# Laser_Sign.net
KiCad netlist of a schematic drawn in EasyEDA
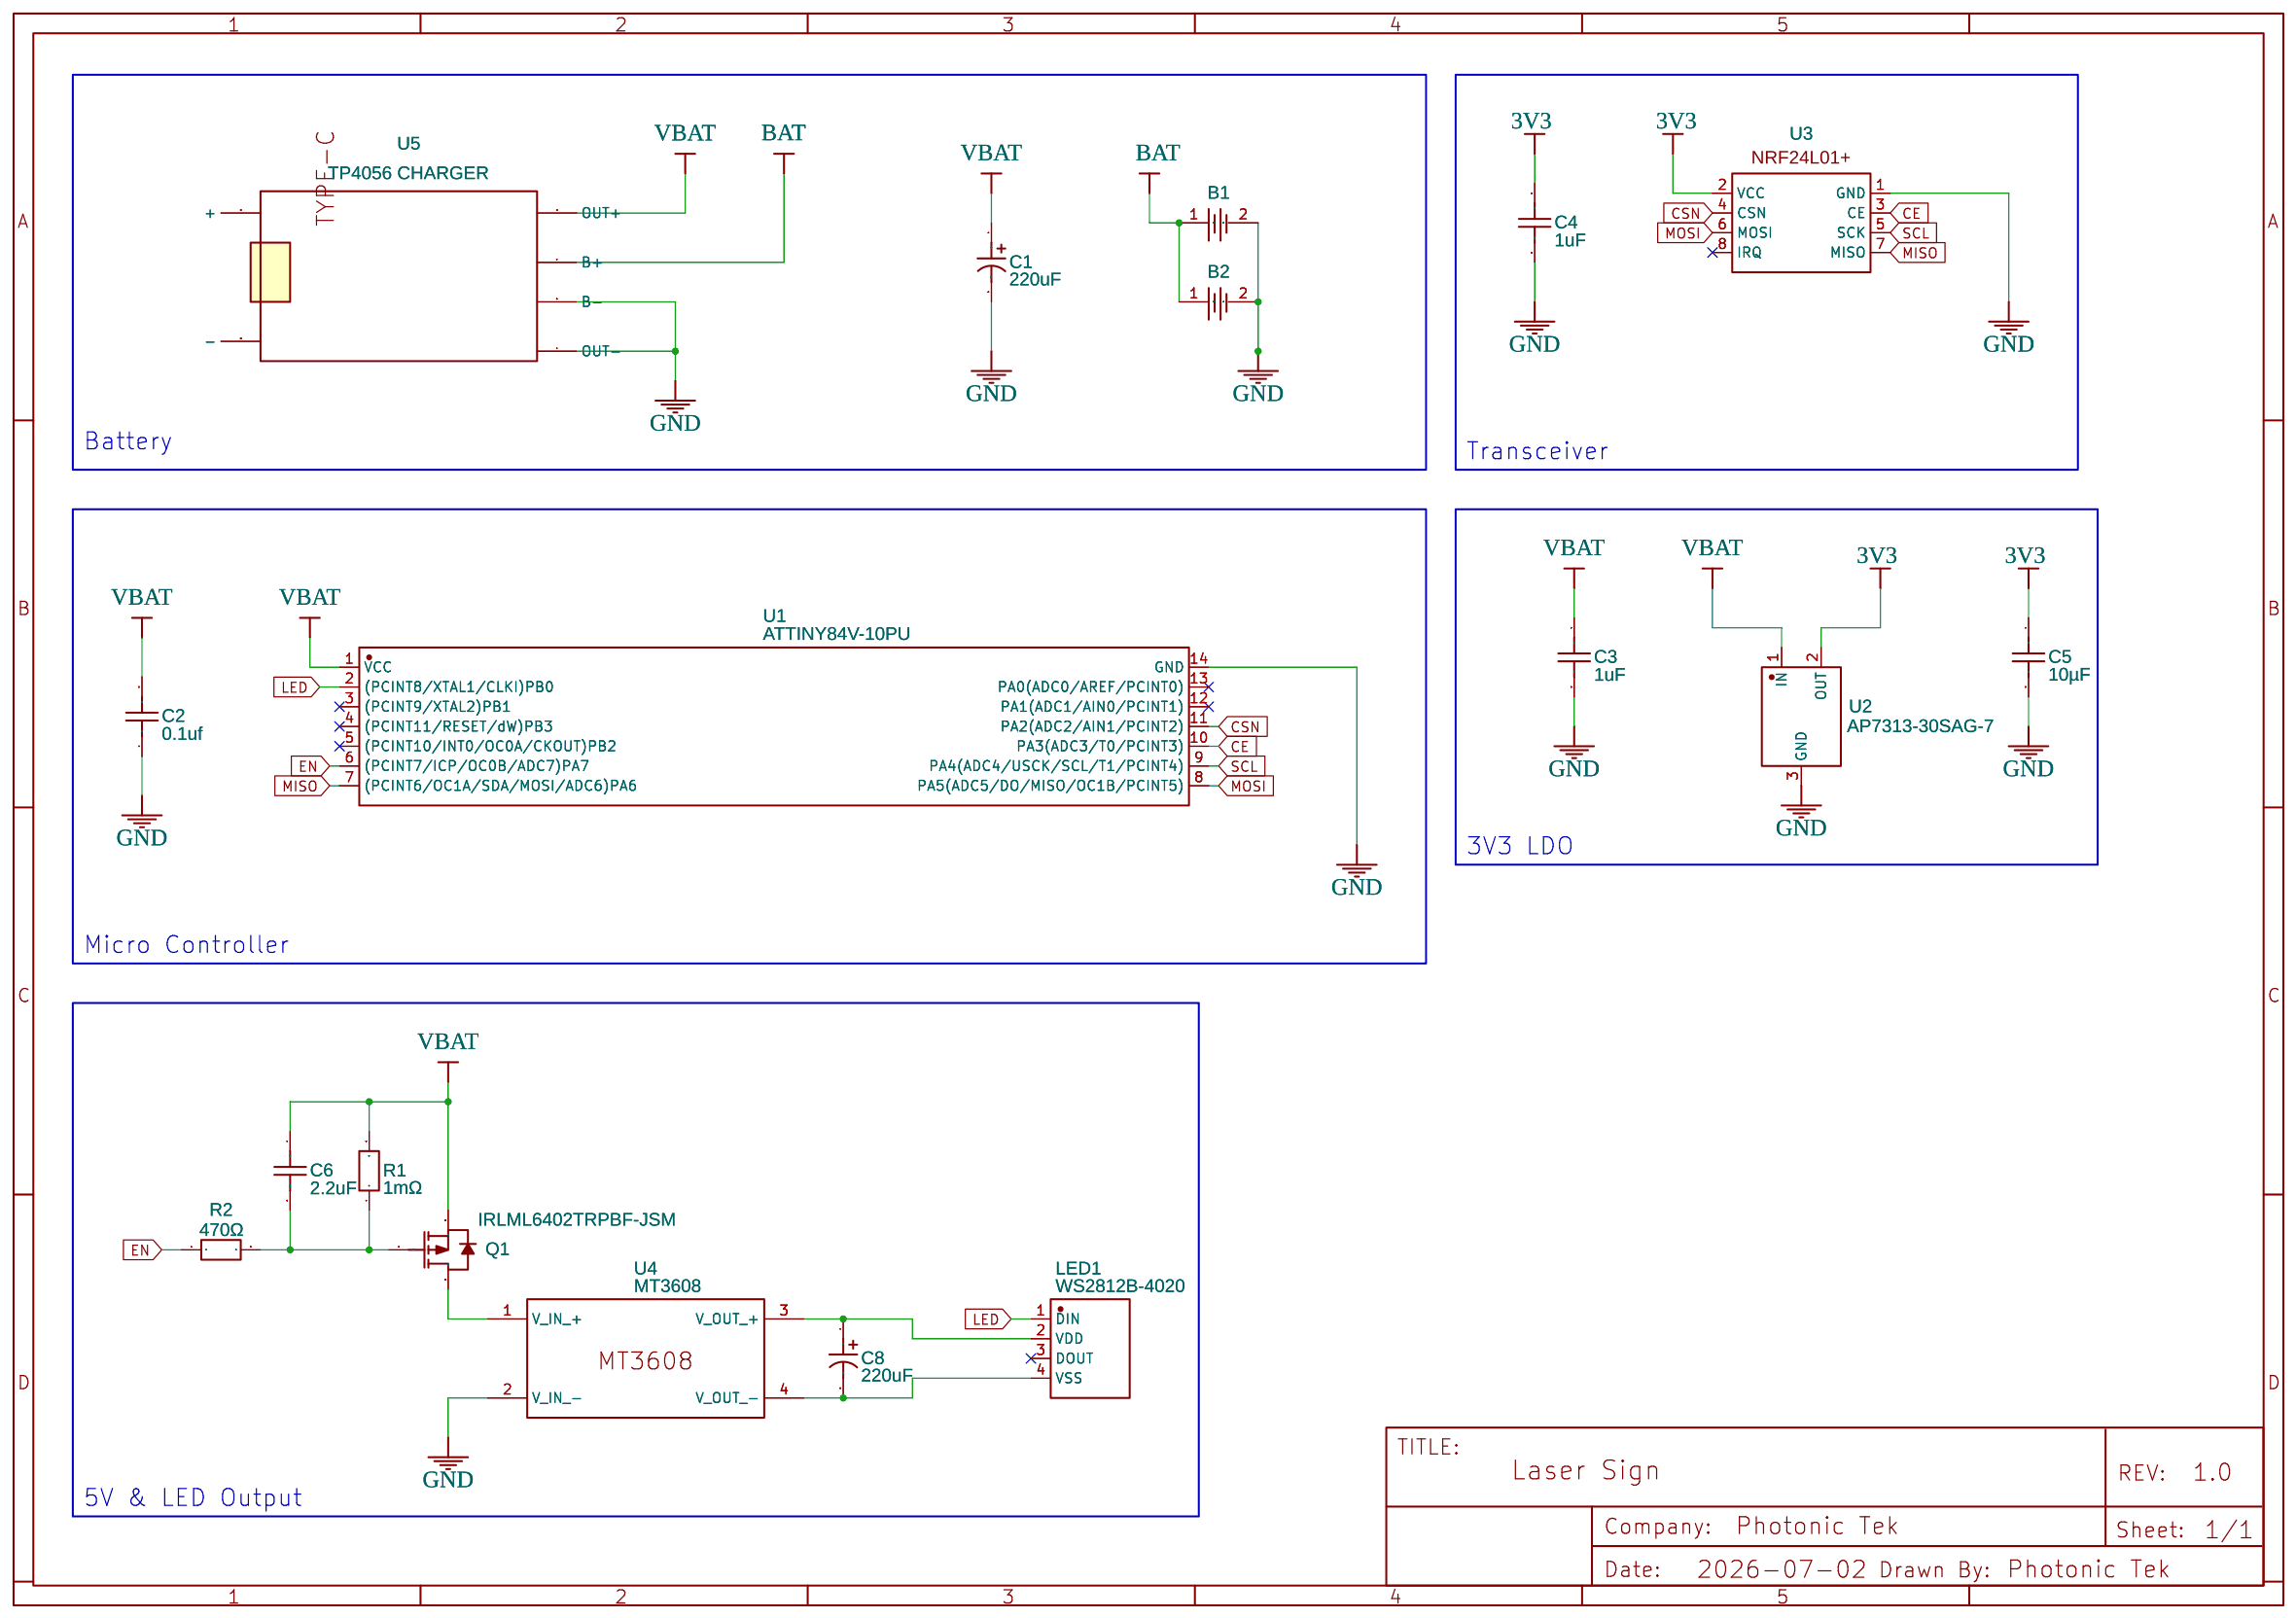
[diagram p0: Sheet_1]
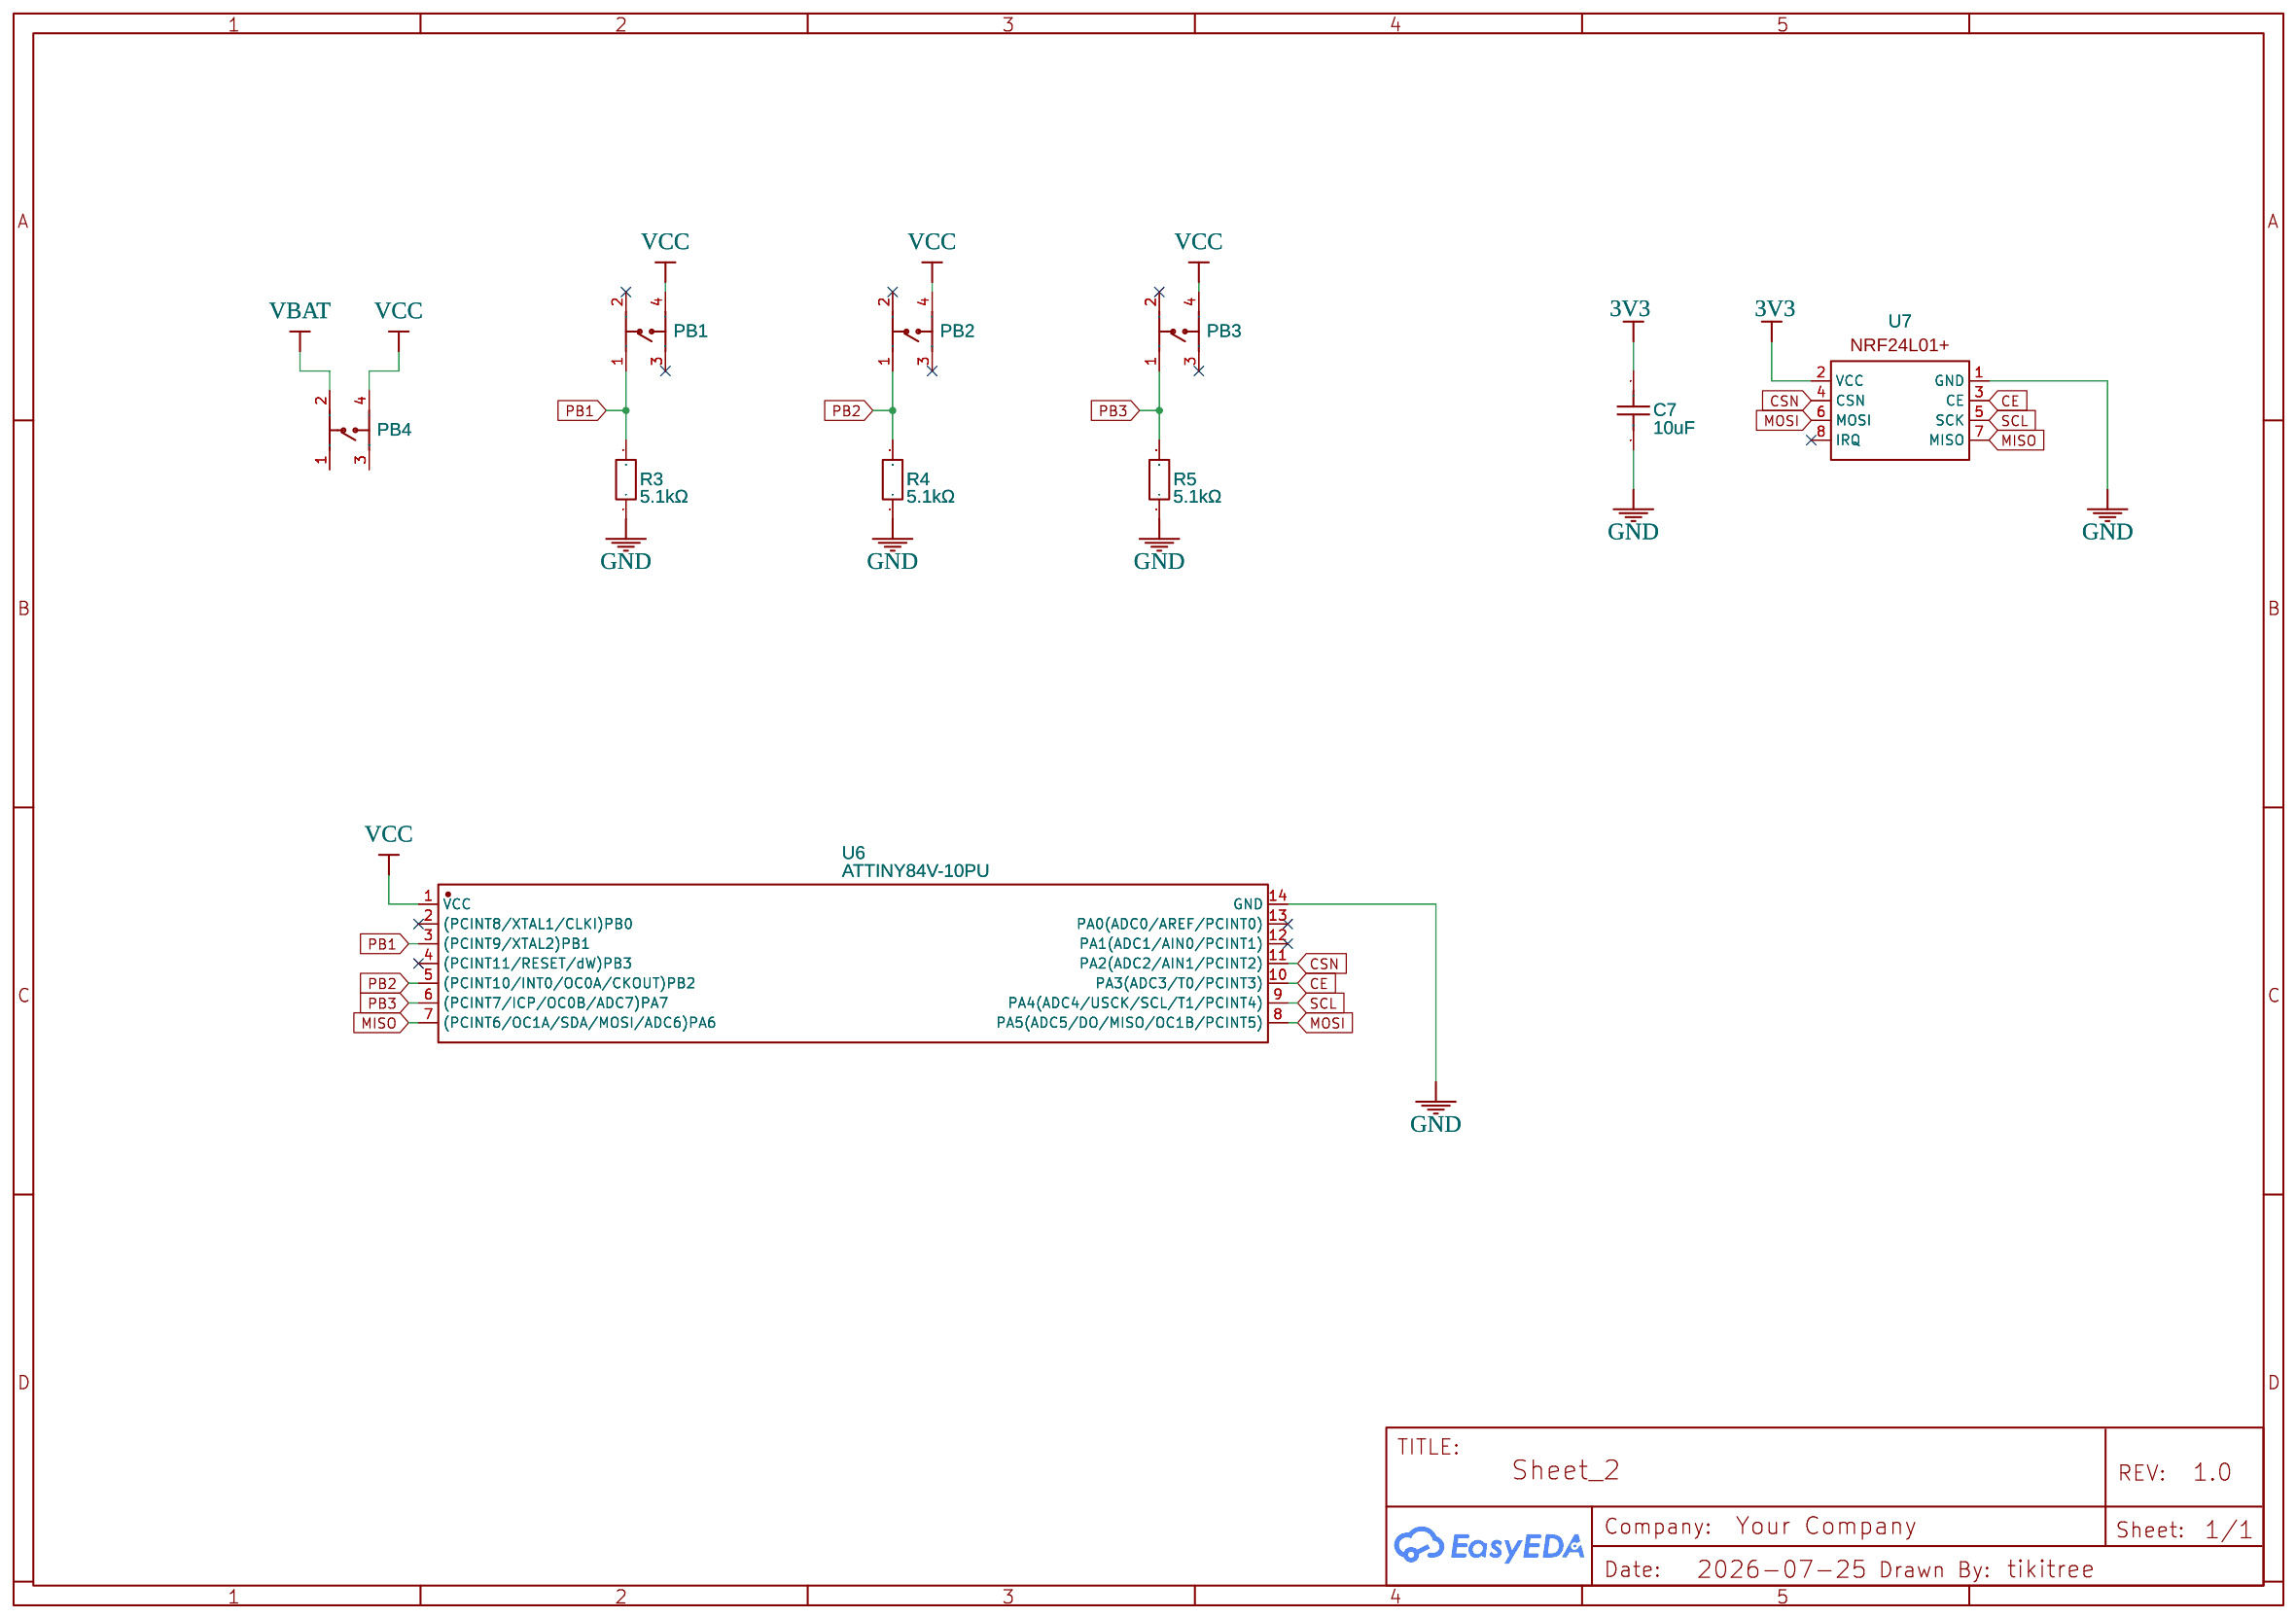
[diagram p1: Sheet_2]

(export (version "E")
  (design (tool "Eeschema 10.0.6"))
  (components
    (comp (ref "B1")
      (value "CR1220-2")
      (fields (field (name "Manufacturer") "Q&J"))
      (libsource (lib "") (part "CR1220-2"))
    )
    (comp (ref "B2")
      (value "CR1220-2")
      (fields (field (name "Manufacturer") "Q&J"))
      (libsource (lib "") (part "CR1220-2"))
    )
    (comp (ref "C1")
      (value "220uF")
      (fields (field (name "Manufacturer Part") "ERG50V220M10X13") (field (name "Manufacturer") "JIERR(捷而瑞)"))
      (libsource (lib "") (part "ERG50V220M10X13"))
    )
    (comp (ref "C2") (value "0.1uf") (libsource (lib "") (part "GE CERAMIC CAPACITOR")))
    (comp (ref "C3")
      (value "1uF")
      (fields (field (name "Manufacturer Part") "08053C105JAT2A") (field (name "Manufacturer") "KYOCERA AVX"))
      (libsource (lib "") (part "08053C105JAT2A"))
    )
    (comp (ref "C4")
      (value "1uF")
      (fields (field (name "Manufacturer Part") "08053C105JAT2A") (field (name "Manufacturer") "KYOCERA AVX"))
      (libsource (lib "") (part "08053C105JAT2A"))
    )
    (comp (ref "C5")
      (value "10µF")
      (fields
        (field (name "Manufacturer Part") "CL10A106MA8NRNC")
        (field (name "Manufacturer") "Samsung Electro-Mechanics")
      )
      (libsource (lib "") (part "CL10A106MA8NRNC"))
    )
    (comp (ref "C6")
      (value "2.2uF")
      (fields (field (name "Manufacturer Part") "08053C105JAT2A") (field (name "Manufacturer") "KYOCERA AVX"))
      (libsource (lib "") (part "08053C105JAT2A"))
    )
    (comp (ref "C8")
      (value "220uF")
      (fields (field (name "Manufacturer Part") "ERG50V220M10X13") (field (name "Manufacturer") "JIERR(捷而瑞)"))
      (libsource (lib "") (part "ERG50V220M10X13"))
    )
    (comp (ref "LED1")
      (value "WS2812B-4020")
      (fields (field (name "Manufacturer") "worldsemi"))
      (libsource (lib "") (part "WS2812B-4020"))
    )
    (comp (ref "Q1")
      (value "IRLML6402TRPBF-JSM")
      (fields (field (name "Manufacturer") "JSMSEMI(杰盛微)"))
      (libsource (lib "") (part "IRLML6402TRPBF-JSM"))
    )
    (comp (ref "R1")
      (value "1mΩ")
      (fields (field (name "Manufacturer Part") "TP810PW10K0JE") (field (name "Manufacturer") "Ohmite"))
      (libsource (lib "") (part "TP810PW10K0JE_1"))
    )
    (comp (ref "R2")
      (value "470Ω")
      (fields (field (name "Manufacturer Part") "TP810PW10K0JE") (field (name "Manufacturer") "Ohmite"))
      (libsource (lib "") (part "TP810PW10K0JE"))
    )
    (comp (ref "U1") (value "ATTINY84V-10PU") (libsource (lib "") (part "ATTINY84V-10PU")))
    (comp (ref "U2")
      (value "AP7313-30SAG-7")
      (fields (field (name "Manufacturer") "DIODES(美台)"))
      (libsource (lib "") (part "AP7313-30SAG-7"))
    )
    (comp (ref "U3") (value "NRF24L01+") (libsource (lib "") (part "NRF24L01+")))
    (comp (ref "U4") (value "MT3608") (libsource (lib "") (part "MT3608")))
    (comp (ref "U5")
      (value "TP4056 CHARGER")
      (fields (field (name "Manufacturer Part") "TP4056"))
      (libsource (lib "") (part "TP4056 CHARGING MODDULE"))
    )
    (comp (ref "C7")
      (value "10uF")
      (fields (field (name "Manufacturer Part") "08053C105JAT2A") (field (name "Manufacturer") "KYOCERA AVX"))
      (libsource (lib "") (part "08053C105JAT2A"))
    )
    (comp (ref "PB1")
      (value "TSC005A2526B")
      (fields (field (name "Manufacturer") "BZCN(博众电气)"))
      (libsource (lib "") (part "TSC005A2526B"))
    )
    (comp (ref "PB2")
      (value "TSC005A2526B")
      (fields (field (name "Manufacturer") "BZCN(博众电气)"))
      (libsource (lib "") (part "TSC005A2526B"))
    )
    (comp (ref "PB3")
      (value "TSC005A2526B")
      (fields (field (name "Manufacturer") "BZCN(博众电气)"))
      (libsource (lib "") (part "TSC005A2526B"))
    )
    (comp (ref "PB4")
      (value "TSC005A2526B")
      (fields (field (name "Manufacturer") "BZCN(博众电气)"))
      (libsource (lib "") (part "TSC005A2526B"))
    )
    (comp (ref "R3")
      (value "5.1kΩ")
      (fields (field (name "Manufacturer Part") "ERJP06J512V") (field (name "Manufacturer") "PANASONIC(松下)"))
      (libsource (lib "") (part "ERJP06J512V"))
    )
    (comp (ref "R4")
      (value "5.1kΩ")
      (fields (field (name "Manufacturer Part") "ERJP06J512V") (field (name "Manufacturer") "PANASONIC(松下)"))
      (libsource (lib "") (part "ERJP06J512V"))
    )
    (comp (ref "R5")
      (value "5.1kΩ")
      (fields (field (name "Manufacturer Part") "ERJP06J512V") (field (name "Manufacturer") "PANASONIC(松下)"))
      (libsource (lib "") (part "ERJP06J512V"))
    )
    (comp (ref "U6") (value "ATTINY84V-10PU") (libsource (lib "") (part "ATTINY84V-10PU")))
    (comp (ref "U7") (value "NRF24L01+") (libsource (lib "") (part "NRF24L01+")))
  )
  (nets
    (net (code "1") (name "3V3") (class "Default")
      (node (ref "C4") (pin "1") (pinfunction "1_1") (pintype "unspecified"))
      (node (ref "C5") (pin "1") (pinfunction "1_1") (pintype "unspecified"))
      (node (ref "C7") (pin "1") (pinfunction "1_1") (pintype "unspecified"))
      (node (ref "U2") (pin "2") (pinfunction "OUT_2") (pintype "unspecified"))
      (node (ref "U3") (pin "2") (pinfunction "VCC_2") (pintype "unspecified"))
      (node (ref "U7") (pin "2") (pinfunction "VCC_2") (pintype "unspecified"))
    )
    (net (code "2") (name "BAT") (class "Default")
      (node (ref "B1") (pin "1") (pinfunction "1_1") (pintype "input"))
      (node (ref "B2") (pin "1") (pinfunction "1_1") (pintype "input"))
    )
    (net (code "3") (name "CE") (class "Default")
      (node (ref "U1") (pin "10") (pinfunction "PA3(ADC3/T0/PCINT3)_10") (pintype "unspecified"))
      (node (ref "U3") (pin "3") (pinfunction "CE_3") (pintype "unspecified"))
      (node (ref "U6") (pin "10") (pinfunction "PA3(ADC3/T0/PCINT3)_10") (pintype "unspecified"))
      (node (ref "U7") (pin "3") (pinfunction "CE_3") (pintype "unspecified"))
    )
    (net (code "4") (name "CSN") (class "Default")
      (node (ref "U1") (pin "11") (pinfunction "PA2(ADC2/AIN1/PCINT2)_11") (pintype "unspecified"))
      (node (ref "U3") (pin "4") (pinfunction "CSN_4") (pintype "unspecified"))
      (node (ref "U6") (pin "11") (pinfunction "PA2(ADC2/AIN1/PCINT2)_11") (pintype "unspecified"))
      (node (ref "U7") (pin "4") (pinfunction "CSN_4") (pintype "unspecified"))
    )
    (net (code "5") (name "EN") (class "Default")
      (node (ref "R2") (pin "1") (pinfunction "1_1") (pintype "unspecified"))
      (node (ref "U1") (pin "6") (pinfunction "(PCINT7/ICP/OC0B/ADC7)PA7_6") (pintype "unspecified"))
    )
    (net (code "6") (name "GND") (class "Default")
      (node (ref "B1") (pin "2") (pinfunction "2_2") (pintype "input"))
      (node (ref "B2") (pin "2") (pinfunction "2_2") (pintype "input"))
      (node (ref "C1") (pin "2") (pinfunction "2_2") (pintype "input"))
      (node (ref "C2") (pin "1") (pinfunction "1_1") (pintype "unspecified"))
      (node (ref "C3") (pin "2") (pinfunction "2_2") (pintype "unspecified"))
      (node (ref "C4") (pin "2") (pinfunction "2_2") (pintype "unspecified"))
      (node (ref "C5") (pin "2") (pinfunction "2_2") (pintype "unspecified"))
      (node (ref "C7") (pin "2") (pinfunction "2_2") (pintype "unspecified"))
      (node (ref "R3") (pin "1") (pinfunction "1_1") (pintype "unspecified"))
      (node (ref "R4") (pin "1") (pinfunction "1_1") (pintype "unspecified"))
      (node (ref "R5") (pin "1") (pinfunction "1_1") (pintype "unspecified"))
      (node (ref "U1") (pin "14") (pinfunction "GND_14") (pintype "unspecified"))
      (node (ref "U2") (pin "3") (pinfunction "GND_3") (pintype "unspecified"))
      (node (ref "U3") (pin "1") (pinfunction "GND_1") (pintype "unspecified"))
      (node (ref "U4") (pin "2") (pinfunction "V_IN_-_2") (pintype "unspecified"))
      (node (ref "U6") (pin "14") (pinfunction "GND_14") (pintype "unspecified"))
      (node (ref "U7") (pin "1") (pinfunction "GND_1") (pintype "unspecified"))
    )
    (net (code "7") (name "LED") (class "Default")
      (node (ref "LED1") (pin "1") (pinfunction "DIN_1") (pintype "unspecified"))
      (node (ref "U1") (pin "2") (pinfunction "(PCINT8/XTAL1/CLKI)PB0_2") (pintype "unspecified"))
    )
    (net (code "8") (name "MISO") (class "Default")
      (node (ref "U1") (pin "7") (pinfunction "(PCINT6/OC1A/SDA/MOSI/ADC6)PA6_7") (pintype "unspecified"))
      (node (ref "U3") (pin "7") (pinfunction "MISO_7") (pintype "unspecified"))
      (node (ref "U6") (pin "7") (pinfunction "(PCINT6/OC1A/SDA/MOSI/ADC6)PA6_7") (pintype "unspecified"))
      (node (ref "U7") (pin "7") (pinfunction "MISO_7") (pintype "unspecified"))
    )
    (net (code "9") (name "MOSI") (class "Default")
      (node (ref "U1") (pin "8") (pinfunction "PA5(ADC5/DO/MISO/OC1B/PCINT5)_8") (pintype "unspecified"))
      (node (ref "U3") (pin "6") (pinfunction "MOSI_6") (pintype "unspecified"))
      (node (ref "U6") (pin "8") (pinfunction "PA5(ADC5/DO/MISO/OC1B/PCINT5)_8") (pintype "unspecified"))
      (node (ref "U7") (pin "6") (pinfunction "MOSI_6") (pintype "unspecified"))
    )
    (net (code "10") (name "Net-(LED1-VDD)") (class "Default")
      (node (ref "C8") (pin "1") (pinfunction "1_1") (pintype "input"))
      (node (ref "LED1") (pin "2") (pinfunction "VDD_2") (pintype "unspecified"))
      (node (ref "U4") (pin "3") (pinfunction "V_OUT_+_3") (pintype "unspecified"))
    )
    (net (code "11") (name "Net-(LED1-VSS)") (class "Default")
      (node (ref "C8") (pin "2") (pinfunction "2_2") (pintype "input"))
      (node (ref "LED1") (pin "4") (pinfunction "VSS_4") (pintype "unspecified"))
      (node (ref "U4") (pin "4") (pinfunction "V_OUT_-_4") (pintype "unspecified"))
    )
    (net (code "12") (name "Net-(Q1-D)") (class "Default")
      (node (ref "Q1") (pin "3") (pinfunction "D_3") (pintype "unspecified"))
      (node (ref "U4") (pin "1") (pinfunction "V_IN_+_1") (pintype "unspecified"))
    )
    (net (code "13") (name "Net-(Q1-G)") (class "Default")
      (node (ref "C6") (pin "2") (pinfunction "2_2") (pintype "unspecified"))
      (node (ref "Q1") (pin "1") (pinfunction "G_1") (pintype "unspecified"))
      (node (ref "R1") (pin "1") (pinfunction "1_1") (pintype "unspecified"))
      (node (ref "R2") (pin "2") (pinfunction "2_2") (pintype "unspecified"))
    )
    (net (code "14") (name "PB1") (class "Default")
      (node (ref "PB1") (pin "1") (pinfunction "1_1") (pintype "unspecified"))
      (node (ref "R3") (pin "2") (pinfunction "2_2") (pintype "unspecified"))
      (node (ref "U6") (pin "3") (pinfunction "(PCINT9/XTAL2)PB1_3") (pintype "unspecified"))
    )
    (net (code "15") (name "PB2") (class "Default")
      (node (ref "PB2") (pin "1") (pinfunction "1_1") (pintype "unspecified"))
      (node (ref "R4") (pin "2") (pinfunction "2_2") (pintype "unspecified"))
      (node (ref "U6") (pin "5") (pinfunction "(PCINT10/INT0/OC0A/CKOUT)PB2_5") (pintype "unspecified"))
    )
    (net (code "16") (name "PB3") (class "Default")
      (node (ref "PB3") (pin "1") (pinfunction "1_1") (pintype "unspecified"))
      (node (ref "R5") (pin "2") (pinfunction "2_2") (pintype "unspecified"))
      (node (ref "U6") (pin "6") (pinfunction "(PCINT7/ICP/OC0B/ADC7)PA7_6") (pintype "unspecified"))
    )
    (net (code "17") (name "SCL") (class "Default")
      (node (ref "U1") (pin "9") (pinfunction "PA4(ADC4/USCK/SCL/T1/PCINT4)_9") (pintype "unspecified"))
      (node (ref "U3") (pin "5") (pinfunction "SCK_5") (pintype "unspecified"))
      (node (ref "U6") (pin "9") (pinfunction "PA4(ADC4/USCK/SCL/T1/PCINT4)_9") (pintype "unspecified"))
      (node (ref "U7") (pin "5") (pinfunction "SCK_5") (pintype "unspecified"))
    )
    (net (code "18") (name "VBAT") (class "Default")
      (node (ref "C1") (pin "1") (pinfunction "1_1") (pintype "input"))
      (node (ref "C2") (pin "2") (pinfunction "2_2") (pintype "unspecified"))
      (node (ref "C3") (pin "1") (pinfunction "1_1") (pintype "unspecified"))
      (node (ref "C6") (pin "1") (pinfunction "1_1") (pintype "unspecified"))
      (node (ref "PB4") (pin "2") (pinfunction "2_2") (pintype "unspecified"))
      (node (ref "Q1") (pin "2") (pinfunction "S_2") (pintype "unspecified"))
      (node (ref "R1") (pin "2") (pinfunction "2_2") (pintype "unspecified"))
      (node (ref "U1") (pin "1") (pinfunction "VCC_1") (pintype "unspecified"))
      (node (ref "U2") (pin "1") (pinfunction "IN_1") (pintype "unspecified"))
    )
    (net (code "19") (name "VCC") (class "Default")
      (node (ref "PB1") (pin "4") (pinfunction "4_4") (pintype "unspecified"))
      (node (ref "PB2") (pin "4") (pinfunction "4_4") (pintype "unspecified"))
      (node (ref "PB3") (pin "4") (pinfunction "4_4") (pintype "unspecified"))
      (node (ref "PB4") (pin "4") (pinfunction "4_4") (pintype "unspecified"))
      (node (ref "U6") (pin "1") (pinfunction "VCC_1") (pintype "unspecified"))
    )
    (net (code "20") (name "unconnected-(LED1-DOUT-Pad3)") (class "Default")
      (node (ref "LED1") (pin "3") (pinfunction "DOUT_3") (pintype "unspecified+no_connect"))
    )
    (net (code "21") (name "unconnected-(PB1-Pad2)") (class "Default")
      (node (ref "PB1") (pin "2") (pinfunction "2_2") (pintype "unspecified+no_connect"))
    )
    (net (code "22") (name "unconnected-(PB1-Pad3)") (class "Default")
      (node (ref "PB1") (pin "3") (pinfunction "3_3") (pintype "unspecified+no_connect"))
    )
    (net (code "23") (name "unconnected-(PB2-Pad2)") (class "Default")
      (node (ref "PB2") (pin "2") (pinfunction "2_2") (pintype "unspecified+no_connect"))
    )
    (net (code "24") (name "unconnected-(PB2-Pad3)") (class "Default")
      (node (ref "PB2") (pin "3") (pinfunction "3_3") (pintype "unspecified+no_connect"))
    )
    (net (code "25") (name "unconnected-(PB3-Pad2)") (class "Default")
      (node (ref "PB3") (pin "2") (pinfunction "2_2") (pintype "unspecified+no_connect"))
    )
    (net (code "26") (name "unconnected-(PB3-Pad3)") (class "Default")
      (node (ref "PB3") (pin "3") (pinfunction "3_3") (pintype "unspecified+no_connect"))
    )
    (net (code "27") (name "unconnected-(PB4-Pad1)") (class "Default")
      (node (ref "PB4") (pin "1") (pinfunction "1_1") (pintype "unspecified"))
    )
    (net (code "28") (name "unconnected-(PB4-Pad3)") (class "Default")
      (node (ref "PB4") (pin "3") (pinfunction "3_3") (pintype "unspecified"))
    )
    (net (code "29") (name "unconnected-(U1-(PCINT9{slash}XTAL2)PB1-Pad3)") (class "Default")
      (node (ref "U1") (pin "3") (pinfunction "(PCINT9/XTAL2)PB1_3") (pintype "unspecified+no_connect"))
    )
    (net (code "30") (name "unconnected-(U1-(PCINT10{slash}INT0{slash}OC0A{slash}CKOUT)PB2-Pad5)") (class "Default")
      (node (ref "U1") (pin "5") (pinfunction "(PCINT10/INT0/OC0A/CKOUT)PB2_5") (pintype "unspecified+no_connect"))
    )
    (net (code "31") (name "unconnected-(U1-(PCINT11{slash}RESET{slash}dW)PB3-Pad4)") (class "Default")
      (node (ref "U1") (pin "4") (pinfunction "(PCINT11/RESET/dW)PB3_4") (pintype "unspecified+no_connect"))
    )
    (net (code "32") (name "unconnected-(U1-PA0(ADC0{slash}AREF{slash}PCINT0)-Pad13)") (class "Default")
      (node (ref "U1") (pin "13") (pinfunction "PA0(ADC0/AREF/PCINT0)_13") (pintype "unspecified+no_connect"))
    )
    (net (code "33") (name "unconnected-(U1-PA1(ADC1{slash}AIN0{slash}PCINT1)-Pad12)") (class "Default")
      (node (ref "U1") (pin "12") (pinfunction "PA1(ADC1/AIN0/PCINT1)_12") (pintype "unspecified+no_connect"))
    )
    (net (code "34") (name "unconnected-(U3-IRQ-Pad8)") (class "Default")
      (node (ref "U3") (pin "8") (pinfunction "IRQ_8") (pintype "unspecified+no_connect"))
    )
    (net (code "35") (name "unconnected-(U5-+-Pad5)") (class "Default")
      (node (ref "U5") (pin "5") (pinfunction "+_5") (pintype "unspecified"))
    )
    (net (code "36") (name "unconnected-(U5---Pad6)") (class "Default")
      (node (ref "U5") (pin "6") (pinfunction "-_6") (pintype "unspecified"))
    )
    (net (code "37") (name "unconnected-(U5-B+-Pad1)") (class "Default")
      (node (ref "U5") (pin "1") (pinfunction "B+_1") (pintype "unspecified"))
    )
    (net (code "38") (name "unconnected-(U5-B--Pad2)") (class "Default")
      (node (ref "U5") (pin "2") (pinfunction "B-_2") (pintype "unspecified"))
    )
    (net (code "39") (name "unconnected-(U5-OUT+-Pad3)") (class "Default")
      (node (ref "U5") (pin "3") (pinfunction "OUT+_3") (pintype "unspecified"))
    )
    (net (code "40") (name "unconnected-(U5-OUT--Pad4)") (class "Default")
      (node (ref "U5") (pin "4") (pinfunction "OUT-_4") (pintype "unspecified"))
    )
    (net (code "41") (name "unconnected-(U6-(PCINT8{slash}XTAL1{slash}CLKI)PB0-Pad2)") (class "Default")
      (node (ref "U6") (pin "2") (pinfunction "(PCINT8/XTAL1/CLKI)PB0_2") (pintype "unspecified+no_connect"))
    )
    (net (code "42") (name "unconnected-(U6-(PCINT11{slash}RESET{slash}dW)PB3-Pad4)") (class "Default")
      (node (ref "U6") (pin "4") (pinfunction "(PCINT11/RESET/dW)PB3_4") (pintype "unspecified+no_connect"))
    )
    (net (code "43") (name "unconnected-(U6-PA0(ADC0{slash}AREF{slash}PCINT0)-Pad13)") (class "Default")
      (node (ref "U6") (pin "13") (pinfunction "PA0(ADC0/AREF/PCINT0)_13") (pintype "unspecified+no_connect"))
    )
    (net (code "44") (name "unconnected-(U6-PA1(ADC1{slash}AIN0{slash}PCINT1)-Pad12)") (class "Default")
      (node (ref "U6") (pin "12") (pinfunction "PA1(ADC1/AIN0/PCINT1)_12") (pintype "unspecified+no_connect"))
    )
    (net (code "45") (name "unconnected-(U7-IRQ-Pad8)") (class "Default")
      (node (ref "U7") (pin "8") (pinfunction "IRQ_8") (pintype "unspecified+no_connect"))
    )
  )
)
